# leds_et_motor.net
KiCad netlist of a schematic drawn in EAGLE
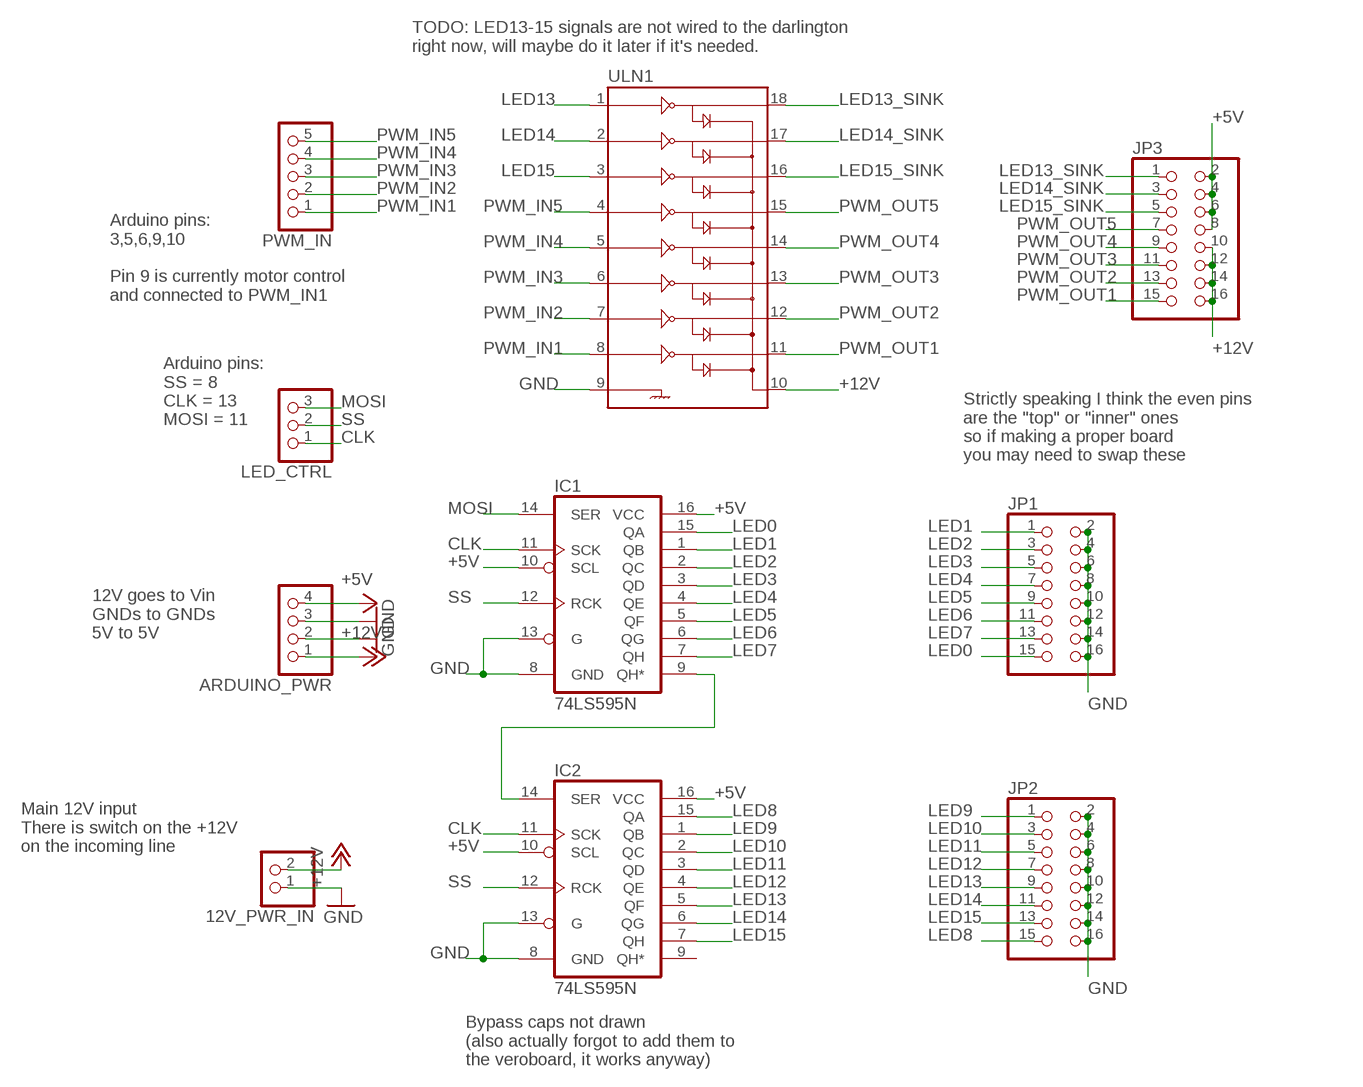
[diagram p0: schematic, sheet 1]

(export (version "E")
  (design (tool "Eeschema 10.0.6"))
  (components
    (comp (ref "12V_PWR_IN")
      (value "PINHD-1X2")
      (footprint "eagle-import:1X02")
      (libsource (lib "eagle-import") (part "PINHD-1X2"))
    )
    (comp (ref "ARDUINO_PWR")
      (value "PINHD-1X4")
      (footprint "eagle-import:1X04")
      (libsource (lib "eagle-import") (part "PINHD-1X4"))
    )
    (comp (ref "IC1")
      (value "74LS595N")
      (footprint "eagle-import:DIL16")
      (libsource (lib "eagle-import") (part "74595NLS"))
    )
    (comp (ref "IC2")
      (value "74LS595N")
      (footprint "eagle-import:DIL16")
      (libsource (lib "eagle-import") (part "74595NLS"))
    )
    (comp (ref "JP1")
      (value "PINHD-2X8/90")
      (footprint "eagle-import:2X08_90")
      (libsource (lib "eagle-import") (part "PINHD-2X8/90"))
    )
    (comp (ref "JP2")
      (value "PINHD-2X8/90")
      (footprint "eagle-import:2X08_90")
      (libsource (lib "eagle-import") (part "PINHD-2X8/90"))
    )
    (comp (ref "JP3")
      (value "PINHD-2X8/90")
      (footprint "eagle-import:2X08_90")
      (libsource (lib "eagle-import") (part "PINHD-2X8/90"))
    )
    (comp (ref "LED_CTRL")
      (value "PINHD-1X3")
      (footprint "eagle-import:1X03")
      (libsource (lib "eagle-import") (part "PINHD-1X3"))
    )
    (comp (ref "PWM_IN")
      (value "PINHD-1X5")
      (footprint "eagle-import:1X05")
      (libsource (lib "eagle-import") (part "PINHD-1X5"))
    )
    (comp (ref "ULN1")
      (value "ULN2803DIP")
      (footprint "eagle-import:DIL18")
      (libsource (lib "eagle-import") (part "ULN2803DIP"))
    )
  )
  (nets
    (net (code "1") (name "+5V") (class "Default")
      (node (ref "ARDUINO_PWR") (pin "4") (pinfunction "4_4") (pintype "passive"))
      (node (ref "IC1") (pin "10") (pinfunction "SCL_10") (pintype "input"))
      (node (ref "IC1") (pin "16") (pinfunction "VCC_16") (pintype "power_in"))
      (node (ref "IC2") (pin "10") (pinfunction "SCL_10") (pintype "input"))
      (node (ref "IC2") (pin "16") (pinfunction "VCC_16") (pintype "power_in"))
      (node (ref "JP3") (pin "2") (pinfunction "2_2") (pintype "passive"))
      (node (ref "JP3") (pin "4") (pinfunction "4_4") (pintype "passive"))
      (node (ref "JP3") (pin "6") (pinfunction "6_6") (pintype "passive"))
      (node (ref "JP3") (pin "8") (pinfunction "8_8") (pintype "passive"))
    )
    (net (code "2") (name "+12V") (class "Default")
      (node (ref "12V_PWR_IN") (pin "2") (pinfunction "2_2") (pintype "passive"))
      (node (ref "ARDUINO_PWR") (pin "1") (pinfunction "1_1") (pintype "passive"))
      (node (ref "JP3") (pin "10") (pinfunction "10_10") (pintype "passive"))
      (node (ref "JP3") (pin "12") (pinfunction "12_12") (pintype "passive"))
      (node (ref "JP3") (pin "14") (pinfunction "14_14") (pintype "passive"))
      (node (ref "JP3") (pin "16") (pinfunction "16_16") (pintype "passive"))
      (node (ref "ULN1") (pin "10") (pinfunction "10_10") (pintype "bidirectional"))
    )
    (net (code "3") (name "/CLK") (class "Default")
      (node (ref "IC1") (pin "11") (pinfunction "SCK_11") (pintype "input"))
      (node (ref "IC2") (pin "11") (pinfunction "SCK_11") (pintype "input"))
      (node (ref "LED_CTRL") (pin "1") (pinfunction "1_1") (pintype "passive"))
    )
    (net (code "4") (name "/LED0") (class "Default")
      (node (ref "IC1") (pin "15") (pinfunction "QA_15") (pintype "tri_state"))
      (node (ref "JP1") (pin "15") (pinfunction "15_15") (pintype "passive"))
    )
    (net (code "5") (name "/LED1") (class "Default")
      (node (ref "IC1") (pin "1") (pinfunction "QB_1") (pintype "tri_state"))
      (node (ref "JP1") (pin "1") (pinfunction "1_1") (pintype "passive"))
    )
    (net (code "6") (name "/LED2") (class "Default")
      (node (ref "IC1") (pin "2") (pinfunction "QC_2") (pintype "tri_state"))
      (node (ref "JP1") (pin "3") (pinfunction "3_3") (pintype "passive"))
    )
    (net (code "7") (name "/LED3") (class "Default")
      (node (ref "IC1") (pin "3") (pinfunction "QD_3") (pintype "tri_state"))
      (node (ref "JP1") (pin "5") (pinfunction "5_5") (pintype "passive"))
    )
    (net (code "8") (name "/LED4") (class "Default")
      (node (ref "IC1") (pin "4") (pinfunction "QE_4") (pintype "tri_state"))
      (node (ref "JP1") (pin "7") (pinfunction "7_7") (pintype "passive"))
    )
    (net (code "9") (name "/LED5") (class "Default")
      (node (ref "IC1") (pin "5") (pinfunction "QF_5") (pintype "tri_state"))
      (node (ref "JP1") (pin "9") (pinfunction "9_9") (pintype "passive"))
    )
    (net (code "10") (name "/LED6") (class "Default")
      (node (ref "IC1") (pin "6") (pinfunction "QG_6") (pintype "tri_state"))
      (node (ref "JP1") (pin "11") (pinfunction "11_11") (pintype "passive"))
    )
    (net (code "11") (name "/LED7") (class "Default")
      (node (ref "IC1") (pin "7") (pinfunction "QH_7") (pintype "tri_state"))
      (node (ref "JP1") (pin "13") (pinfunction "13_13") (pintype "passive"))
    )
    (net (code "12") (name "/LED8") (class "Default")
      (node (ref "IC2") (pin "15") (pinfunction "QA_15") (pintype "tri_state"))
      (node (ref "JP2") (pin "15") (pinfunction "15_15") (pintype "passive"))
    )
    (net (code "13") (name "/LED9") (class "Default")
      (node (ref "IC2") (pin "1") (pinfunction "QB_1") (pintype "tri_state"))
      (node (ref "JP2") (pin "1") (pinfunction "1_1") (pintype "passive"))
    )
    (net (code "14") (name "/LED10") (class "Default")
      (node (ref "IC2") (pin "2") (pinfunction "QC_2") (pintype "tri_state"))
      (node (ref "JP2") (pin "3") (pinfunction "3_3") (pintype "passive"))
    )
    (net (code "15") (name "/LED11") (class "Default")
      (node (ref "IC2") (pin "3") (pinfunction "QD_3") (pintype "tri_state"))
      (node (ref "JP2") (pin "5") (pinfunction "5_5") (pintype "passive"))
    )
    (net (code "16") (name "/LED12") (class "Default")
      (node (ref "IC2") (pin "4") (pinfunction "QE_4") (pintype "tri_state"))
      (node (ref "JP2") (pin "7") (pinfunction "7_7") (pintype "passive"))
    )
    (net (code "17") (name "/LED13") (class "Default")
      (node (ref "IC2") (pin "5") (pinfunction "QF_5") (pintype "tri_state"))
      (node (ref "JP2") (pin "9") (pinfunction "9_9") (pintype "passive"))
      (node (ref "ULN1") (pin "1") (pinfunction "1_1") (pintype "bidirectional"))
    )
    (net (code "18") (name "/LED13_SINK") (class "Default")
      (node (ref "JP3") (pin "1") (pinfunction "1_1") (pintype "passive"))
      (node (ref "ULN1") (pin "18") (pinfunction "18_18") (pintype "bidirectional"))
    )
    (net (code "19") (name "/LED14") (class "Default")
      (node (ref "IC2") (pin "6") (pinfunction "QG_6") (pintype "tri_state"))
      (node (ref "JP2") (pin "11") (pinfunction "11_11") (pintype "passive"))
      (node (ref "ULN1") (pin "2") (pinfunction "2_2") (pintype "bidirectional"))
    )
    (net (code "20") (name "/LED14_SINK") (class "Default")
      (node (ref "JP3") (pin "3") (pinfunction "3_3") (pintype "passive"))
      (node (ref "ULN1") (pin "17") (pinfunction "17_17") (pintype "bidirectional"))
    )
    (net (code "21") (name "/LED15") (class "Default")
      (node (ref "IC2") (pin "7") (pinfunction "QH_7") (pintype "tri_state"))
      (node (ref "JP2") (pin "13") (pinfunction "13_13") (pintype "passive"))
      (node (ref "ULN1") (pin "3") (pinfunction "3_3") (pintype "bidirectional"))
    )
    (net (code "22") (name "/LED15_SINK") (class "Default")
      (node (ref "JP3") (pin "5") (pinfunction "5_5") (pintype "passive"))
      (node (ref "ULN1") (pin "16") (pinfunction "16_16") (pintype "bidirectional"))
    )
    (net (code "23") (name "/MOSI") (class "Default")
      (node (ref "IC1") (pin "14") (pinfunction "SER_14") (pintype "input"))
      (node (ref "LED_CTRL") (pin "3") (pinfunction "3_3") (pintype "passive"))
    )
    (net (code "24") (name "/PWM_IN1") (class "Default")
      (node (ref "PWM_IN") (pin "1") (pinfunction "1_1") (pintype "passive"))
      (node (ref "ULN1") (pin "8") (pinfunction "8_8") (pintype "bidirectional"))
    )
    (net (code "25") (name "/PWM_IN2") (class "Default")
      (node (ref "PWM_IN") (pin "2") (pinfunction "2_2") (pintype "passive"))
      (node (ref "ULN1") (pin "7") (pinfunction "7_7") (pintype "bidirectional"))
    )
    (net (code "26") (name "/PWM_IN3") (class "Default")
      (node (ref "PWM_IN") (pin "3") (pinfunction "3_3") (pintype "passive"))
      (node (ref "ULN1") (pin "6") (pinfunction "6_6") (pintype "bidirectional"))
    )
    (net (code "27") (name "/PWM_IN4") (class "Default")
      (node (ref "PWM_IN") (pin "4") (pinfunction "4_4") (pintype "passive"))
      (node (ref "ULN1") (pin "5") (pinfunction "5_5") (pintype "bidirectional"))
    )
    (net (code "28") (name "/PWM_IN5") (class "Default")
      (node (ref "PWM_IN") (pin "5") (pinfunction "5_5") (pintype "passive"))
      (node (ref "ULN1") (pin "4") (pinfunction "4_4") (pintype "bidirectional"))
    )
    (net (code "29") (name "/PWM_OUT1") (class "Default")
      (node (ref "JP3") (pin "15") (pinfunction "15_15") (pintype "passive"))
      (node (ref "ULN1") (pin "11") (pinfunction "11_11") (pintype "bidirectional"))
    )
    (net (code "30") (name "/PWM_OUT2") (class "Default")
      (node (ref "JP3") (pin "13") (pinfunction "13_13") (pintype "passive"))
      (node (ref "ULN1") (pin "12") (pinfunction "12_12") (pintype "bidirectional"))
    )
    (net (code "31") (name "/PWM_OUT3") (class "Default")
      (node (ref "JP3") (pin "11") (pinfunction "11_11") (pintype "passive"))
      (node (ref "ULN1") (pin "13") (pinfunction "13_13") (pintype "bidirectional"))
    )
    (net (code "32") (name "/PWM_OUT4") (class "Default")
      (node (ref "JP3") (pin "9") (pinfunction "9_9") (pintype "passive"))
      (node (ref "ULN1") (pin "14") (pinfunction "14_14") (pintype "bidirectional"))
    )
    (net (code "33") (name "/PWM_OUT5") (class "Default")
      (node (ref "JP3") (pin "7") (pinfunction "7_7") (pintype "passive"))
      (node (ref "ULN1") (pin "15") (pinfunction "15_15") (pintype "bidirectional"))
    )
    (net (code "34") (name "/SS") (class "Default")
      (node (ref "IC1") (pin "12") (pinfunction "RCK_12") (pintype "input"))
      (node (ref "IC2") (pin "12") (pinfunction "RCK_12") (pintype "input"))
      (node (ref "LED_CTRL") (pin "2") (pinfunction "2_2") (pintype "passive"))
    )
    (net (code "35") (name "GND") (class "Default")
      (node (ref "12V_PWR_IN") (pin "1") (pinfunction "1_1") (pintype "passive"))
      (node (ref "ARDUINO_PWR") (pin "2") (pinfunction "2_2") (pintype "passive"))
      (node (ref "ARDUINO_PWR") (pin "3") (pinfunction "3_3") (pintype "passive"))
      (node (ref "IC1") (pin "13") (pinfunction "G_13") (pintype "input"))
      (node (ref "IC1") (pin "8") (pinfunction "GND_8") (pintype "power_in"))
      (node (ref "IC2") (pin "13") (pinfunction "G_13") (pintype "input"))
      (node (ref "IC2") (pin "8") (pinfunction "GND_8") (pintype "power_in"))
      (node (ref "JP1") (pin "10") (pinfunction "10_10") (pintype "passive"))
      (node (ref "JP1") (pin "12") (pinfunction "12_12") (pintype "passive"))
      (node (ref "JP1") (pin "14") (pinfunction "14_14") (pintype "passive"))
      (node (ref "JP1") (pin "16") (pinfunction "16_16") (pintype "passive"))
      (node (ref "JP1") (pin "2") (pinfunction "2_2") (pintype "passive"))
      (node (ref "JP1") (pin "4") (pinfunction "4_4") (pintype "passive"))
      (node (ref "JP1") (pin "6") (pinfunction "6_6") (pintype "passive"))
      (node (ref "JP1") (pin "8") (pinfunction "8_8") (pintype "passive"))
      (node (ref "JP2") (pin "10") (pinfunction "10_10") (pintype "passive"))
      (node (ref "JP2") (pin "12") (pinfunction "12_12") (pintype "passive"))
      (node (ref "JP2") (pin "14") (pinfunction "14_14") (pintype "passive"))
      (node (ref "JP2") (pin "16") (pinfunction "16_16") (pintype "passive"))
      (node (ref "JP2") (pin "2") (pinfunction "2_2") (pintype "passive"))
      (node (ref "JP2") (pin "4") (pinfunction "4_4") (pintype "passive"))
      (node (ref "JP2") (pin "6") (pinfunction "6_6") (pintype "passive"))
      (node (ref "JP2") (pin "8") (pinfunction "8_8") (pintype "passive"))
      (node (ref "ULN1") (pin "9") (pinfunction "9_9") (pintype "bidirectional"))
    )
    (net (code "36") (name "Net-(IC1-QH*)") (class "Default")
      (node (ref "IC1") (pin "9") (pinfunction "QH*_9") (pintype "tri_state"))
      (node (ref "IC2") (pin "14") (pinfunction "SER_14") (pintype "input"))
    )
    (net (code "37") (name "unconnected-(IC2-QH*-Pad9)") (class "Default")
      (node (ref "IC2") (pin "9") (pinfunction "QH*_9") (pintype "tri_state"))
    )
  )
)
